# ESP-WROOM32.net
KiCad netlist of a schematic drawn in Altium Designer
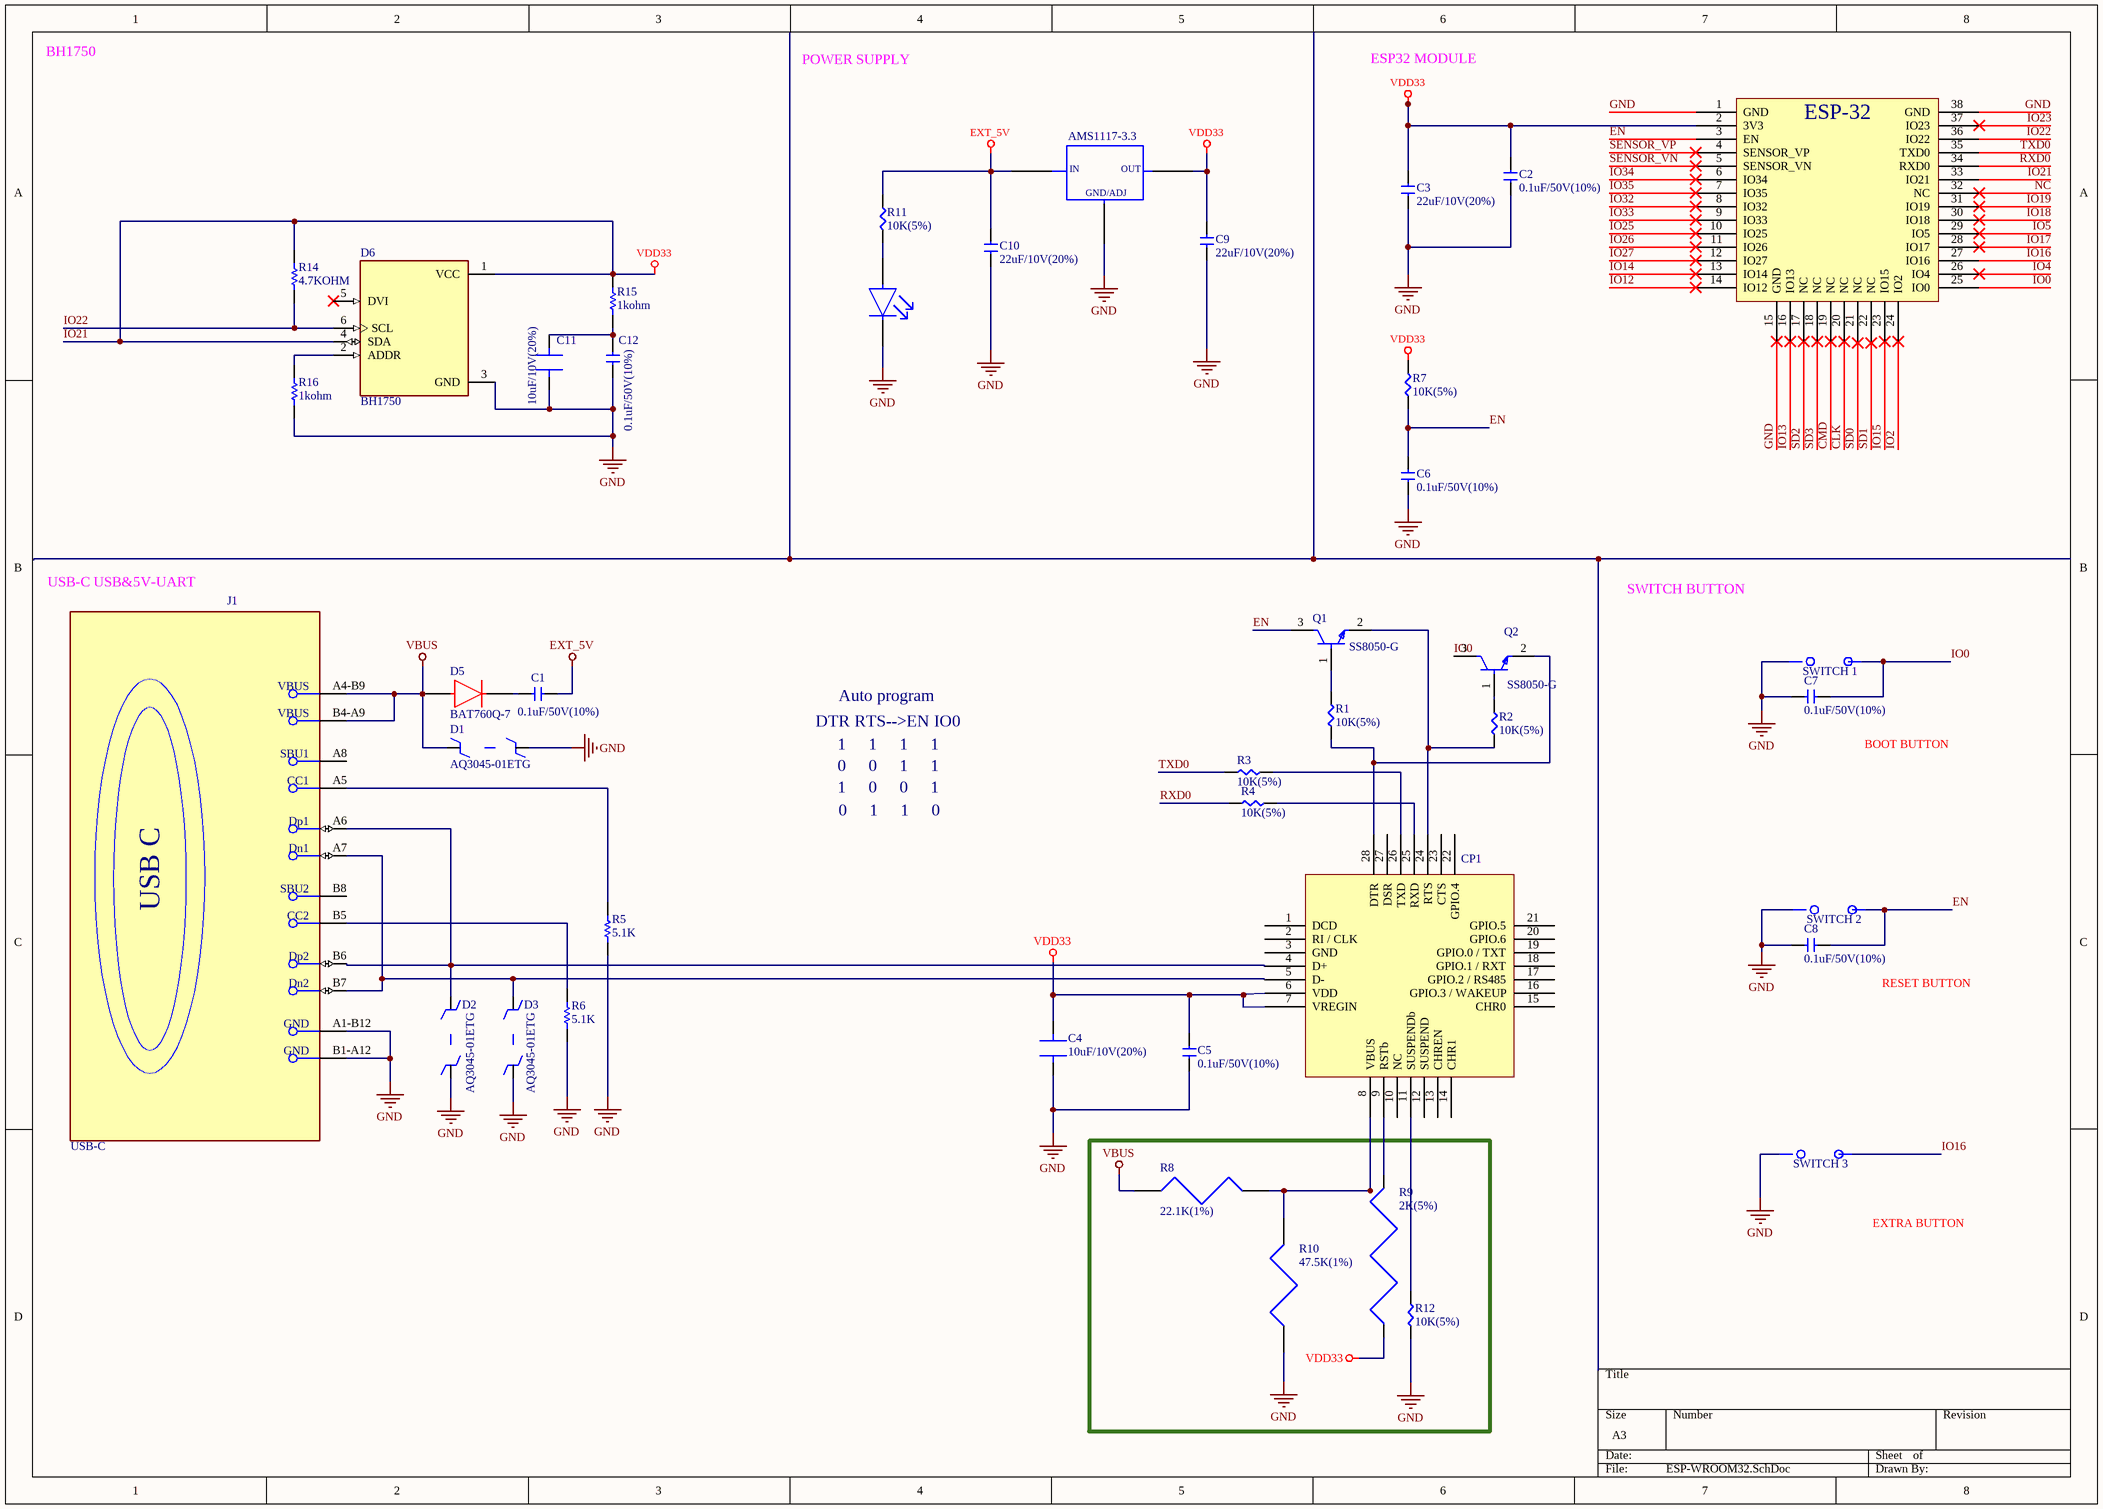
[diagram p0: ESP-WROOM32.SchDoc]

(export (version "E")
  (design (tool "Eeschema 10.0.6"))
  (components
    (comp (ref "*1")
      (value "ESP32-WROOM-32E-N4")
      (footprint "MODULE_ESP-WROOM-32")
      (description "RF TXRX MOD BT WIFI TH SMD")
      (fields (field (name "MANUFACTURER") "Espressif Systems") (field (name "LCSC PART NUMBER") "C701341"))
      (libsource (lib "Librayryschematic") (part "ESP32-WROOM-32E-N4"))
    )
    (comp (ref "C1")
      (value "0.1uF/50V(10%)")
      (footprint "FP-GRM158-0_2-IPC_A")
      (description "CAP CER 0.1UF 50V X7R 0402")
      (fields
        (field (name "MANUFACTURER") "Samsung Electro-Mechanics")
        (field (name "MANUFACTURER PART NUMBER") "CL05B104KB5NNWC")
      )
      (libsource (lib "Librayryschematic") (part "CL05B104KB5NNWC"))
    )
    (comp (ref "C2")
      (value "0.1uF/50V(10%)")
      (footprint "FP-GRM158-0_2-IPC_A")
      (description "CAP CER 0.1UF 50V X7R 0402")
      (fields
        (field (name "MANUFACTURER") "Samsung Electro-Mechanics")
        (field (name "MANUFACTURER PART NUMBER") "CL05B104KB5NNWC")
      )
      (libsource (lib "Librayryschematic") (part "CL05B104KB5NNWC"))
    )
    (comp (ref "C3")
      (value "22uF/10V(20%)")
      (footprint "FP-GRM158-0_2-IPC_A")
      (description "CAP CER 22UF 10V X5R 0402")
      (fields
        (field (name "MANUFACTURER") "Murata")
        (field (name "MANUFACTURER PART NUMBER") "GRM158R61A226ME15D")
      )
      (libsource (lib "Librayryschematic") (part "GRM158R61A226ME15D"))
    )
    (comp (ref "C4")
      (value "10uF/10V(20%)")
      (footprint "FP-GRM158-0_2-IPC_A")
      (description "CAP CER 10UF 10V X5R 0402")
      (fields
        (field (name "MANUFACTURER") "Yageo Group")
        (field (name "MANUFACTURER PART NUMBER") "CC0402MRX5R6BB106")
      )
      (libsource (lib "Librayryschematic") (part "CC0402MRX5R6BB106"))
    )
    (comp (ref "C5")
      (value "0.1uF/50V(10%)")
      (footprint "FP-GRM158-0_2-IPC_A")
      (description "CAP CER 0.1UF 50V X7R 0402")
      (fields
        (field (name "MANUFACTURER") "Samsung Electro-Mechanics")
        (field (name "MANUFACTURER PART NUMBER") "CL05B104KB5NNWC")
      )
      (libsource (lib "Librayryschematic") (part "CL05B104KB5NNWC"))
    )
    (comp (ref "C6")
      (value "0.1uF/50V(10%)")
      (footprint "FP-GRM158-0_2-IPC_A")
      (description "CAP CER 0.1UF 50V X7R 0402")
      (fields
        (field (name "MANUFACTURER") "Samsung Electro-Mechanics")
        (field (name "MANUFACTURER PART NUMBER") "CL05B104KB5NNWC")
      )
      (libsource (lib "Librayryschematic") (part "CL05B104KB5NNWC"))
    )
    (comp (ref "C7")
      (value "0.1uF/50V(10%)")
      (footprint "FP-GRM158-0_2-IPC_A")
      (description "CAP CER 0.1UF 50V X7R 0402")
      (fields
        (field (name "MANUFACTURER") "Samsung Electro-Mechanics")
        (field (name "MANUFACTURER PART NUMBER") "CL05B104KB5NNWC")
      )
      (libsource (lib "Librayryschematic") (part "CL05B104KB5NNWC"))
    )
    (comp (ref "C8")
      (value "0.1uF/50V(10%)")
      (footprint "FP-GRM158-0_2-IPC_A")
      (description "CAP CER 0.1UF 50V X7R 0402")
      (fields
        (field (name "MANUFACTURER") "Samsung Electro-Mechanics")
        (field (name "MANUFACTURER PART NUMBER") "CL05B104KB5NNWC")
      )
      (libsource (lib "Librayryschematic") (part "CL05B104KB5NNWC"))
    )
    (comp (ref "C9")
      (value "22uF/10V(20%)")
      (footprint "FP-GRM158-0_2-IPC_A")
      (description "CAP CER 22UF 10V X5R 0402")
      (fields
        (field (name "MANUFACTURER") "Murata")
        (field (name "MANUFACTURER PART NUMBER") "GRM158R61A226ME15D")
      )
      (libsource (lib "Librayryschematic") (part "GRM158R61A226ME15D"))
    )
    (comp (ref "C10")
      (value "22uF/10V(20%)")
      (footprint "FP-GRM158-0_2-IPC_A")
      (description "CAP CER 22UF 10V X5R 0402")
      (fields
        (field (name "MANUFACTURER") "Murata")
        (field (name "MANUFACTURER PART NUMBER") "GRM158R61A226ME15D")
      )
      (libsource (lib "Librayryschematic") (part "GRM158R61A226ME15D"))
    )
    (comp (ref "C11")
      (value "10uF/10V(20%)")
      (footprint "FP-GRM158-0_2-IPC_A")
      (description "CAP CER 10UF 10V X5R 0402")
      (fields
        (field (name "MANUFACTURER") "Yageo Group")
        (field (name "MANUFACTURER PART NUMBER") "CC0402MRX5R6BB106")
      )
      (libsource (lib "Librayryschematic") (part "CC0402MRX5R6BB106"))
    )
    (comp (ref "C12")
      (value "0.1uF/50V(10%)")
      (footprint "FP-GRM158-0_2-IPC_A")
      (description "CAP CER 0.1UF 50V X7R 0402")
      (fields
        (field (name "MANUFACTURER") "Samsung Electro-Mechanics")
        (field (name "MANUFACTURER PART NUMBER") "CL05B104KB5NNWC")
      )
      (libsource (lib "Librayryschematic") (part "CL05B104KB5NNWC"))
    )
    (comp (ref "CP1")
      (value "CP2102N-A02-GQFN28")
      (footprint "FP-CP2102N-A02-GQFN28-IPC_A")
      (description "USB Bridge, USB to UART USB 2.0 UART Interface 28-QFN (5x5)")
      (fields (field (name "MANUFACTURER") "Silicon Labs") (field (name "LCSC PART NUMBER") "C964632"))
      (libsource (lib "Librayryschematic") (part "CP2102N-A02-GQFN28"))
    )
    (comp (ref "D1")
      (value "AQ3045-01ETG")
      (footprint "PESD5V0U1BA,115")
      (description "TVS DIODE 5.3VWM 12VC SOD882")
      (fields (field (name "MANUFACTURER") "Littelfuse") (field (name "LCSC PART NUMBER") "C3710326"))
      (libsource (lib "Librayryschematic") (part "AQ3045-01ETG"))
    )
    (comp (ref "D2")
      (value "AQ3045-01ETG")
      (footprint "PESD5V0U1BA,115")
      (description "TVS DIODE 5.3VWM 12VC SOD882")
      (fields (field (name "MANUFACTURER") "Littelfuse") (field (name "LCSC PART NUMBER") "C3710326"))
      (libsource (lib "Librayryschematic") (part "AQ3045-01ETG"))
    )
    (comp (ref "D3")
      (value "AQ3045-01ETG")
      (footprint "PESD5V0U1BA,115")
      (description "TVS DIODE 5.3VWM 12VC SOD882")
      (fields (field (name "MANUFACTURER") "Littelfuse") (field (name "LCSC PART NUMBER") "C3710326"))
      (libsource (lib "Librayryschematic") (part "AQ3045-01ETG"))
    )
    (comp (ref "D4")
      (value "LTST-C170GKT")
      (footprint "FP-LTST-C170GKT-MFG")
      (description "LED GREEN CLEAR SMD")
      (fields (field (name "MANUFACTURER") "Lite-On") (field (name "VOLTAGE") "5V"))
      (libsource (lib "Librayryschematic") (part "LTST-C170GKT"))
    )
    (comp (ref "D5")
      (value "BAT760Q-7")
      (footprint "BAT760Q-7")
      (description "DIODE SCHOTTKY 30V 1A SOD323")
      (fields (field (name "MANUFACTURER") "Diodes Inc.") (field (name "LCSC PART NUMBER") "C3759252"))
      (libsource (lib "Librayryschematic") (part "BAT760Q-7"))
    )
    (comp (ref "D6")
      (value "BH1750")
      (footprint "XDCR_BH1750FVI-TR")
      (description "SENSOR OPT 560NM AMBIENT 6WSOF")
      (fields (field (name "MANUFACTURER") "ROHM") (field (name "MANUFACTURER PART NUMBER") "BH1750FVI-TR"))
      (libsource (lib "Librayryschematic") (part "BH1750FVI-TR"))
    )
    (comp (ref "J1")
      (value "USB-C")
      (footprint "FP-2171790001-MFG")
      (description "CONN RCP USB2.0 TYP C 24P SMD RA")
      (fields (field (name "MANUFACTURER") "Molex") (field (name "MANUFACTURER PART NUMBER") "217179-0001"))
      (libsource (lib "Librayryschematic") (part "2171790001"))
    )
    (comp (ref "Q1")
      (value "SS8050-G")
      (footprint "FP-SS8050-G-IPC_A")
      (description "TRANS NPN 25V 1.5A SOT-23-3")
      (fields (field (name "MANUFACTURER") "Comchip") (field (name "LCSC PART NUMBER") "C164886"))
      (libsource (lib "Librayryschematic") (part "SS8050-G"))
    )
    (comp (ref "Q2")
      (value "SS8050-G")
      (footprint "FP-SS8050-G-IPC_A")
      (description "TRANS NPN 25V 1.5A SOT-23-3")
      (fields (field (name "MANUFACTURER") "Comchip") (field (name "LCSC PART NUMBER") "C164886"))
      (libsource (lib "Librayryschematic") (part "SS8050-G"))
    )
    (comp (ref "R1")
      (value "10K(5%)")
      (footprint "RESC1005X40X25LL05T10")
      (description "RES 10K OHM 5% 1/16W 0402")
      (fields
        (field (name "MANUFACTURER") "Yageo Group")
        (field (name "MANUFACTURER PART NUMBER") "RC0402JR-0710KL")
      )
      (libsource (lib "Librayryschematic") (part "RC0402JR-0710KL"))
    )
    (comp (ref "R2")
      (value "10K(5%)")
      (footprint "RESC1005X40X25LL05T10")
      (description "RES 10K OHM 5% 1/16W 0402")
      (fields
        (field (name "MANUFACTURER") "Yageo Group")
        (field (name "MANUFACTURER PART NUMBER") "RC0402JR-0710KL")
      )
      (libsource (lib "Librayryschematic") (part "RC0402JR-0710KL"))
    )
    (comp (ref "R3")
      (value "10K(5%)")
      (footprint "RESC1005X40X25LL05T10")
      (description "RES 10K OHM 5% 1/16W 0402")
      (fields
        (field (name "MANUFACTURER") "Yageo Group")
        (field (name "MANUFACTURER PART NUMBER") "RC0402JR-0710KL")
      )
      (libsource (lib "Librayryschematic") (part "RC0402JR-0710KL"))
    )
    (comp (ref "R4")
      (value "10K(5%)")
      (footprint "RESC1005X40X25LL05T10")
      (description "RES 10K OHM 5% 1/16W 0402")
      (fields
        (field (name "MANUFACTURER") "Yageo Group")
        (field (name "MANUFACTURER PART NUMBER") "RC0402JR-0710KL")
      )
      (libsource (lib "Librayryschematic") (part "RC0402JR-0710KL"))
    )
    (comp (ref "R5")
      (value "5.1K")
      (footprint "RESC1005X40X25LL05T10")
      (description "RES 5.1K OHM 1% 1/16W 0402")
      (fields
        (field (name "MANUFACTURER") "Yageo Group")
        (field (name "MANUFACTURER PART NUMBER") "RC0402FR-075K1L")
      )
      (libsource (lib "Librayryschematic") (part "RC0402FR-075K1L"))
    )
    (comp (ref "R6")
      (value "5.1K")
      (footprint "RESC1005X40X25LL05T10")
      (description "RES 5.1K OHM 1% 1/16W 0402")
      (fields
        (field (name "MANUFACTURER") "Yageo Group")
        (field (name "MANUFACTURER PART NUMBER") "RC0402FR-075K1L")
      )
      (libsource (lib "Librayryschematic") (part "RC0402FR-075K1L"))
    )
    (comp (ref "R7")
      (value "10K(5%)")
      (footprint "RESC1005X40X25LL05T10")
      (description "RES 10K OHM 5% 1/16W 0402")
      (fields
        (field (name "MANUFACTURER") "Yageo Group")
        (field (name "MANUFACTURER PART NUMBER") "RC0402JR-0710KL")
      )
      (libsource (lib "Librayryschematic") (part "RC0402JR-0710KL"))
    )
    (comp (ref "R8")
      (value "22.1K(1%)")
      (footprint "RESC1005X40X25LL05T10")
      (description "RES SMD 22.1K OHM 1% 1/16W 0402")
      (fields
        (field (name "MANUFACTURER") "Yageo Group")
        (field (name "MANUFACTURER PART NUMBER") "AC0402FR-0722K1L")
      )
      (libsource (lib "Librayryschematic") (part "AC0402FR-0722K1L"))
    )
    (comp (ref "R9")
      (value "2K(5%)")
      (footprint "RESC1005X40X25LL05T10")
      (description "RES 2K OHM 5% 1/16W 0402")
      (fields
        (field (name "MANUFACTURER") "Yageo Group")
        (field (name "MANUFACTURER PART NUMBER") "RC0402JR-072KL")
      )
      (libsource (lib "Librayryschematic") (part "RC0402JR-072KL"))
    )
    (comp (ref "R10")
      (value "47.5K(1%)")
      (footprint "RESC1005X40X25LL05T10")
      (description "RES 47.5K OHM 1% 1/16W 0402")
      (fields
        (field (name "MANUFACTURER") "Yageo Group")
        (field (name "MANUFACTURER PART NUMBER") "RC0402FR-1347K5L")
      )
      (libsource (lib "Librayryschematic") (part "RC0402FR-1347K5L"))
    )
    (comp (ref "R11")
      (value "10K(5%)")
      (footprint "RESC1005X40X25LL05T10")
      (description "RES 10K OHM 5% 1/16W 0402")
      (fields
        (field (name "MANUFACTURER") "Yageo Group")
        (field (name "MANUFACTURER PART NUMBER") "RC0402JR-0710KL")
      )
      (libsource (lib "Librayryschematic") (part "RC0402JR-0710KL"))
    )
    (comp (ref "R12")
      (value "10K(5%)")
      (footprint "RESC1005X40X25LL05T10")
      (description "RES 10K OHM 5% 1/16W 0402")
      (fields
        (field (name "MANUFACTURER") "Yageo Group")
        (field (name "MANUFACTURER PART NUMBER") "RC0402JR-0710KL")
      )
      (libsource (lib "Librayryschematic") (part "RC0402JR-0710KL"))
    )
    (comp (ref "R14")
      (value "4.7KOHM")
      (footprint "RESC1005X40X25LL05T10")
      (description "RES 4.7K OHM 5% 1/16W 0402")
      (fields
        (field (name "MANUFACTURER") "Yageo Group")
        (field (name "MANUFACTURER PART NUMBER") "RC0402JR-0747KL")
      )
      (libsource (lib "Librayryschematic") (part "RC0402JR-0747KL"))
    )
    (comp (ref "R15")
      (value "1kohm")
      (footprint "RESC1005X40X25LL05T10")
      (description "RES 1K OHM 5% 1/16W 0402")
      (fields
        (field (name "MANUFACTURER") "Yageo Group")
        (field (name "MANUFACTURER PART NUMBER") "RC0402JR-071KL")
      )
      (libsource (lib "Librayryschematic") (part "RC0402JR-071KL"))
    )
    (comp (ref "R16")
      (value "1kohm")
      (footprint "RESC1005X40X25LL05T10")
      (description "RES 1K OHM 5% 1/16W 0402")
      (fields
        (field (name "MANUFACTURER") "Yageo Group")
        (field (name "MANUFACTURER PART NUMBER") "RC0402JR-071KL")
      )
      (libsource (lib "Librayryschematic") (part "RC0402JR-071KL"))
    )
    (comp (ref "SWITCH 1")
      (value "PTS645SL50SMTR92LFS")
      (footprint "FP-PTS645SH50SMTR92LFS-MFG")
      (description "SWITCH TACTILE SPST-NO 0.05A 12V")
      (fields (field (name "MANUFACTURER") "C&K Components") (field (name "LCSC PART NUMBER") "C221877"))
      (libsource (lib "Librayryschematic") (part "PTS645SL50SMTR92LFS"))
    )
    (comp (ref "SWITCH 2")
      (value "PTS645SL50SMTR92LFS")
      (footprint "FP-PTS645SH50SMTR92LFS-MFG")
      (description "SWITCH TACTILE SPST-NO 0.05A 12V")
      (fields (field (name "MANUFACTURER") "C&K Components") (field (name "LCSC PART NUMBER") "C221877"))
      (libsource (lib "Librayryschematic") (part "PTS645SL50SMTR92LFS"))
    )
    (comp (ref "SWITCH 3")
      (value "PTS645SL50SMTR92LFS")
      (footprint "FP-PTS645SH50SMTR92LFS-MFG")
      (description "SWITCH TACTILE SPST-NO 0.05A 12V")
      (fields (field (name "MANUFACTURER") "C&K Components") (field (name "LCSC PART NUMBER") "C221877"))
      (libsource (lib "Librayryschematic") (part "PTS645SL50SMTR92LFS"))
    )
    (comp (ref "U1")
      (value "AMS1117-3.3")
      (footprint "FP-AMS1117-IPC_A")
      (description "IC REG LINEAR 3.3V 1A SOT-223")
      (fields
        (field (name "MANUFACTURER") "UMW(Youtai Semiconductor Co., Ltd.)")
        (field (name "LCSC PART NUMBER") "C6186")
      )
      (libsource (lib "Librayryschematic") (part "AMS1117-3.3"))
    )
  )
  (nets
    (net (code "1") (name "/CLK") (class "Default")
      (node (ref "*1") (pin "20") (pinfunction "NC_20") (pintype "passive+no_connect"))
    )
    (net (code "2") (name "/CMD") (class "Default")
      (node (ref "*1") (pin "19") (pinfunction "NC_19") (pintype "passive+no_connect"))
    )
    (net (code "3") (name "/EN") (class "Default")
      (node (ref "*1") (pin "3") (pinfunction "EN_3") (pintype "passive"))
      (node (ref "C6") (pin "2") (pinfunction "2_2") (pintype "passive"))
      (node (ref "C8") (pin "2") (pinfunction "2_2") (pintype "passive"))
      (node (ref "Q1") (pin "3") (pinfunction "C_3") (pintype "passive"))
      (node (ref "R7") (pin "1") (pinfunction "1_1") (pintype "passive"))
      (node (ref "SWITCH 2") (pin "3") (pinfunction "3_3") (pintype "passive"))
    )
    (net (code "4") (name "/IO0") (class "Default")
      (node (ref "*1") (pin "25") (pinfunction "IO0_25") (pintype "passive"))
      (node (ref "C7") (pin "2") (pinfunction "2_2") (pintype "passive"))
      (node (ref "Q2") (pin "3") (pinfunction "C_3") (pintype "passive"))
      (node (ref "SWITCH 1") (pin "3") (pinfunction "3_3") (pintype "passive"))
    )
    (net (code "5") (name "/IO2") (class "Default")
      (node (ref "*1") (pin "24") (pinfunction "IO2_24") (pintype "passive+no_connect"))
    )
    (net (code "6") (name "/IO4") (class "Default")
      (node (ref "*1") (pin "26") (pinfunction "IO4_26") (pintype "passive+no_connect"))
    )
    (net (code "7") (name "/IO5") (class "Default")
      (node (ref "*1") (pin "29") (pinfunction "IO5_29") (pintype "passive+no_connect"))
    )
    (net (code "8") (name "/IO12") (class "Default")
      (node (ref "*1") (pin "14") (pinfunction "IO12_14") (pintype "passive+no_connect"))
    )
    (net (code "9") (name "/IO13") (class "Default")
      (node (ref "*1") (pin "16") (pinfunction "IO13_16") (pintype "passive+no_connect"))
    )
    (net (code "10") (name "/IO14") (class "Default")
      (node (ref "*1") (pin "13") (pinfunction "IO14_13") (pintype "passive+no_connect"))
    )
    (net (code "11") (name "/IO15") (class "Default")
      (node (ref "*1") (pin "23") (pinfunction "IO15_23") (pintype "passive+no_connect"))
    )
    (net (code "12") (name "/IO16") (class "Default")
      (node (ref "*1") (pin "27") (pinfunction "IO16_27") (pintype "passive"))
      (node (ref "SWITCH 3") (pin "3") (pinfunction "3_3") (pintype "passive"))
    )
    (net (code "13") (name "/IO17") (class "Default")
      (node (ref "*1") (pin "28") (pinfunction "IO17_28") (pintype "passive+no_connect"))
    )
    (net (code "14") (name "/IO18") (class "Default")
      (node (ref "*1") (pin "30") (pinfunction "IO18_30") (pintype "passive+no_connect"))
    )
    (net (code "15") (name "/IO19") (class "Default")
      (node (ref "*1") (pin "31") (pinfunction "IO19_31") (pintype "passive+no_connect"))
    )
    (net (code "16") (name "/IO22") (class "Default")
      (node (ref "*1") (pin "36") (pinfunction "IO22_36") (pintype "passive"))
      (node (ref "D6") (pin "6") (pinfunction "SCL_6") (pintype "input"))
      (node (ref "R14") (pin "2") (pinfunction "2_2") (pintype "passive"))
    )
    (net (code "17") (name "/IO23") (class "Default")
      (node (ref "*1") (pin "37") (pinfunction "IO23_37") (pintype "passive+no_connect"))
    )
    (net (code "18") (name "/IO25") (class "Default")
      (node (ref "*1") (pin "10") (pinfunction "IO25_10") (pintype "passive+no_connect"))
    )
    (net (code "19") (name "/IO26") (class "Default")
      (node (ref "*1") (pin "11") (pinfunction "IO26_11") (pintype "passive+no_connect"))
    )
    (net (code "20") (name "/IO27") (class "Default")
      (node (ref "*1") (pin "12") (pinfunction "IO27_12") (pintype "passive+no_connect"))
    )
    (net (code "21") (name "/IO32") (class "Default")
      (node (ref "*1") (pin "8") (pinfunction "IO32_8") (pintype "passive+no_connect"))
    )
    (net (code "22") (name "/IO33") (class "Default")
      (node (ref "*1") (pin "9") (pinfunction "IO33_9") (pintype "passive+no_connect"))
    )
    (net (code "23") (name "/IO34") (class "Default")
      (node (ref "*1") (pin "6") (pinfunction "IO34_6") (pintype "passive+no_connect"))
    )
    (net (code "24") (name "/IO35") (class "Default")
      (node (ref "*1") (pin "7") (pinfunction "IO35_7") (pintype "passive+no_connect"))
    )
    (net (code "25") (name "/NC") (class "Default")
      (node (ref "*1") (pin "32") (pinfunction "NC_32") (pintype "passive+no_connect"))
    )
    (net (code "26") (name "/RXD0") (class "Default")
      (node (ref "*1") (pin "34") (pinfunction "RXD0_34") (pintype "passive"))
      (node (ref "R4") (pin "1") (pinfunction "1_1") (pintype "passive"))
    )
    (net (code "27") (name "/SD0") (class "Default")
      (node (ref "*1") (pin "21") (pinfunction "NC_21") (pintype "passive"))
    )
    (net (code "28") (name "/SD1") (class "Default")
      (node (ref "*1") (pin "22") (pinfunction "NC_22") (pintype "passive"))
    )
    (net (code "29") (name "/SD2") (class "Default")
      (node (ref "*1") (pin "17") (pinfunction "NC_17") (pintype "passive+no_connect"))
    )
    (net (code "30") (name "/SD3") (class "Default")
      (node (ref "*1") (pin "18") (pinfunction "NC_18") (pintype "passive+no_connect"))
    )
    (net (code "31") (name "/SENSOR_VN") (class "Default")
      (node (ref "*1") (pin "5") (pinfunction "SENSOR_VN_5") (pintype "passive+no_connect"))
    )
    (net (code "32") (name "/SENSOR_VP") (class "Default")
      (node (ref "*1") (pin "4") (pinfunction "SENSOR_VP_4") (pintype "passive+no_connect"))
    )
    (net (code "33") (name "/TXD0") (class "Default")
      (node (ref "*1") (pin "35") (pinfunction "TXD0_35") (pintype "passive"))
      (node (ref "R3") (pin "1") (pinfunction "1_1") (pintype "passive"))
    )
    (net (code "34") (name "EXT_5V") (class "Default")
      (node (ref "C1") (pin "2") (pinfunction "2_2") (pintype "passive"))
      (node (ref "C10") (pin "2") (pinfunction "2_2") (pintype "passive"))
      (node (ref "R11") (pin "2") (pinfunction "2_2") (pintype "passive"))
      (node (ref "U1") (pin "1") (pinfunction "1_1") (pintype "passive"))
    )
    (net (code "35") (name "GND") (class "Default")
      (node (ref "*1") (pin "1") (pinfunction "GND_1") (pintype "passive"))
      (node (ref "*1") (pin "15") (pinfunction "GND_15") (pintype "passive"))
      (node (ref "*1") (pin "38") (pinfunction "GND_38") (pintype "passive"))
      (node (ref "C10") (pin "1") (pinfunction "1_1") (pintype "passive"))
      (node (ref "C11") (pin "1") (pinfunction "1_1") (pintype "passive"))
      (node (ref "C12") (pin "1") (pinfunction "1_1") (pintype "passive"))
      (node (ref "C2") (pin "1") (pinfunction "1_1") (pintype "passive"))
      (node (ref "C3") (pin "1") (pinfunction "1_1") (pintype "passive"))
      (node (ref "C4") (pin "1") (pinfunction "1_1") (pintype "passive"))
      (node (ref "C5") (pin "1") (pinfunction "1_1") (pintype "passive"))
      (node (ref "C6") (pin "1") (pinfunction "1_1") (pintype "passive"))
      (node (ref "C7") (pin "1") (pinfunction "1_1") (pintype "passive"))
      (node (ref "C8") (pin "1") (pinfunction "1_1") (pintype "passive"))
      (node (ref "C9") (pin "1") (pinfunction "1_1") (pintype "passive"))
      (node (ref "D1") (pin "2") (pinfunction "2_2") (pintype "passive"))
      (node (ref "D2") (pin "2") (pinfunction "2_2") (pintype "passive"))
      (node (ref "D3") (pin "2") (pinfunction "2_2") (pintype "passive"))
      (node (ref "D4") (pin "2") (pinfunction "2_2") (pintype "passive"))
      (node (ref "D6") (pin "3") (pinfunction "GND_3") (pintype "power_in"))
      (node (ref "J1") (pin "A1-B12") (pinfunction "GND_A1-B12") (pintype "power_in"))
      (node (ref "J1") (pin "B1-A12") (pinfunction "GND_B1-A12") (pintype "power_in"))
      (node (ref "R10") (pin "1") (pinfunction "1_1") (pintype "passive"))
      (node (ref "R12") (pin "1") (pinfunction "1_1") (pintype "passive"))
      (node (ref "R16") (pin "1") (pinfunction "1_1") (pintype "passive"))
      (node (ref "R5") (pin "1") (pinfunction "1_1") (pintype "passive"))
      (node (ref "R6") (pin "1") (pinfunction "1_1") (pintype "passive"))
      (node (ref "SWITCH 1") (pin "4") (pinfunction "4_4") (pintype "passive"))
      (node (ref "SWITCH 2") (pin "4") (pinfunction "4_4") (pintype "passive"))
      (node (ref "SWITCH 3") (pin "4") (pinfunction "4_4") (pintype "passive"))
      (node (ref "U1") (pin "3") (pinfunction "3_3") (pintype "passive"))
    )
    (net (code "36") (name "Net-(C1-Pad1)") (class "Default")
      (node (ref "C1") (pin "1") (pinfunction "1_1") (pintype "passive"))
      (node (ref "D5") (pin "2") (pinfunction "2_2") (pintype "passive"))
    )
    (net (code "37") (name "Net-(C11-Pad2)") (class "Default")
      (node (ref "C11") (pin "2") (pinfunction "2_2") (pintype "passive"))
      (node (ref "C12") (pin "2") (pinfunction "2_2") (pintype "passive"))
      (node (ref "R15") (pin "1") (pinfunction "1_1") (pintype "passive"))
    )
    (net (code "38") (name "Net-(CP1-D+)") (class "Default")
      (node (ref "CP1") (pin "4") (pinfunction "D+_4") (pintype "passive"))
      (node (ref "D2") (pin "1") (pinfunction "1_1") (pintype "passive"))
      (node (ref "J1") (pin "A6") (pinfunction "Dp1_A6") (pintype "bidirectional"))
      (node (ref "J1") (pin "B6") (pinfunction "Dp2_B6") (pintype "bidirectional"))
    )
    (net (code "39") (name "Net-(CP1-D-)") (class "Default")
      (node (ref "CP1") (pin "5") (pinfunction "D-_5") (pintype "passive"))
      (node (ref "D3") (pin "1") (pinfunction "1_1") (pintype "passive"))
      (node (ref "J1") (pin "A7") (pinfunction "Dn1_A7") (pintype "bidirectional"))
      (node (ref "J1") (pin "B7") (pinfunction "Dn2_B7") (pintype "bidirectional"))
    )
    (net (code "40") (name "Net-(CP1-DTR)") (class "Default")
      (node (ref "CP1") (pin "28") (pinfunction "DTR_28") (pintype "passive"))
      (node (ref "Q2") (pin "2") (pinfunction "E_2") (pintype "passive"))
      (node (ref "R1") (pin "1") (pinfunction "1_1") (pintype "passive"))
    )
    (net (code "41") (name "Net-(CP1-RSTb)") (class "Default")
      (node (ref "CP1") (pin "9") (pinfunction "RSTb_9") (pintype "passive"))
      (node (ref "R9") (pin "2") (pinfunction "2_2") (pintype "passive"))
    )
    (net (code "42") (name "Net-(CP1-RTS)") (class "Default")
      (node (ref "CP1") (pin "24") (pinfunction "RTS_24") (pintype "passive"))
      (node (ref "Q1") (pin "2") (pinfunction "E_2") (pintype "passive"))
      (node (ref "R2") (pin "1") (pinfunction "1_1") (pintype "passive"))
    )
    (net (code "43") (name "Net-(CP1-RXD)") (class "Default")
      (node (ref "CP1") (pin "25") (pinfunction "RXD_25") (pintype "passive"))
      (node (ref "R4") (pin "2") (pinfunction "2_2") (pintype "passive"))
    )
    (net (code "44") (name "Net-(CP1-SUSPENDb)") (class "Default")
      (node (ref "CP1") (pin "11") (pinfunction "SUSPENDb_11") (pintype "passive"))
      (node (ref "R12") (pin "2") (pinfunction "2_2") (pintype "passive"))
    )
    (net (code "45") (name "Net-(CP1-TXD)") (class "Default")
      (node (ref "CP1") (pin "26") (pinfunction "TXD_26") (pintype "passive"))
      (node (ref "R3") (pin "2") (pinfunction "2_2") (pintype "passive"))
    )
    (net (code "46") (name "Net-(CP1-VBUS)") (class "Default")
      (node (ref "CP1") (pin "8") (pinfunction "VBUS_8") (pintype "passive"))
      (node (ref "R10") (pin "2") (pinfunction "2_2") (pintype "passive"))
      (node (ref "R8") (pin "2") (pinfunction "2_2") (pintype "passive"))
    )
    (net (code "47") (name "Net-(D4-Pad1)") (class "Default")
      (node (ref "D4") (pin "1") (pinfunction "1_1") (pintype "passive"))
      (node (ref "R11") (pin "1") (pinfunction "1_1") (pintype "passive"))
    )
    (net (code "48") (name "Net-(D6-ADDR)") (class "Default")
      (node (ref "D6") (pin "2") (pinfunction "ADDR_2") (pintype "input"))
      (node (ref "R16") (pin "2") (pinfunction "2_2") (pintype "passive"))
    )
    (net (code "49") (name "Net-(J1-CC1)") (class "Default")
      (node (ref "J1") (pin "A5") (pinfunction "CC1_A5") (pintype "passive"))
      (node (ref "R5") (pin "2") (pinfunction "2_2") (pintype "passive"))
    )
    (net (code "50") (name "Net-(J1-CC2)") (class "Default")
      (node (ref "J1") (pin "B5") (pinfunction "CC2_B5") (pintype "passive"))
      (node (ref "R6") (pin "2") (pinfunction "2_2") (pintype "passive"))
    )
    (net (code "51") (name "Net-(Q1-B)") (class "Default")
      (node (ref "Q1") (pin "1") (pinfunction "B_1") (pintype "passive"))
      (node (ref "R1") (pin "2") (pinfunction "2_2") (pintype "passive"))
    )
    (net (code "52") (name "Net-(Q2-B)") (class "Default")
      (node (ref "Q2") (pin "1") (pinfunction "B_1") (pintype "passive"))
      (node (ref "R2") (pin "2") (pinfunction "2_2") (pintype "passive"))
    )
    (net (code "53") (name "VBUS") (class "Default")
      (node (ref "D1") (pin "1") (pinfunction "1_1") (pintype "passive"))
      (node (ref "D5") (pin "1") (pinfunction "1_1") (pintype "passive"))
      (node (ref "J1") (pin "A4-B9") (pinfunction "VBUS_A4-B9") (pintype "power_in"))
      (node (ref "J1") (pin "B4-A9") (pinfunction "VBUS_B4-A9") (pintype "power_in"))
      (node (ref "R8") (pin "1") (pinfunction "1_1") (pintype "passive"))
    )
    (net (code "54") (name "VDD33") (class "Default")
      (node (ref "*1") (pin "2") (pinfunction "3V3_2") (pintype "passive"))
      (node (ref "*1") (pin "33") (pinfunction "IO21_33") (pintype "passive"))
      (node (ref "C2") (pin "2") (pinfunction "2_2") (pintype "passive"))
      (node (ref "C3") (pin "2") (pinfunction "2_2") (pintype "passive"))
      (node (ref "C4") (pin "2") (pinfunction "2_2") (pintype "passive"))
      (node (ref "C5") (pin "2") (pinfunction "2_2") (pintype "passive"))
      (node (ref "C9") (pin "2") (pinfunction "2_2") (pintype "passive"))
      (node (ref "CP1") (pin "6") (pinfunction "VDD_6") (pintype "passive"))
      (node (ref "CP1") (pin "7") (pinfunction "VREGIN_7") (pintype "passive"))
      (node (ref "D6") (pin "1") (pinfunction "VCC_1") (pintype "power_in"))
      (node (ref "D6") (pin "4") (pinfunction "SDA_4") (pintype "bidirectional"))
      (node (ref "R14") (pin "1") (pinfunction "1_1") (pintype "passive"))
      (node (ref "R15") (pin "2") (pinfunction "2_2") (pintype "passive"))
      (node (ref "R7") (pin "2") (pinfunction "2_2") (pintype "passive"))
      (node (ref "R9") (pin "1") (pinfunction "1_1") (pintype "passive"))
      (node (ref "U1") (pin "2") (pinfunction "2_2") (pintype "passive"))
    )
    (net (code "55") (name "unconnected-(CP1-CHR0-Pad15)") (class "Default")
      (node (ref "CP1") (pin "15") (pinfunction "CHR0_15") (pintype "passive"))
    )
    (net (code "56") (name "unconnected-(CP1-CHR1-Pad14)") (class "Default")
      (node (ref "CP1") (pin "14") (pinfunction "CHR1_14") (pintype "passive"))
    )
    (net (code "57") (name "unconnected-(CP1-CHREN-Pad13)") (class "Default")
      (node (ref "CP1") (pin "13") (pinfunction "CHREN_13") (pintype "passive"))
    )
    (net (code "58") (name "unconnected-(CP1-CTS-Pad23)") (class "Default")
      (node (ref "CP1") (pin "23") (pinfunction "CTS_23") (pintype "passive"))
    )
    (net (code "59") (name "unconnected-(CP1-DCD-Pad1)") (class "Default")
      (node (ref "CP1") (pin "1") (pinfunction "DCD_1") (pintype "passive"))
    )
    (net (code "60") (name "unconnected-(CP1-DSR-Pad27)") (class "Default")
      (node (ref "CP1") (pin "27") (pinfunction "DSR_27") (pintype "passive"))
    )
    (net (code "61") (name "unconnected-(CP1-GND-Pad3)") (class "Default")
      (node (ref "CP1") (pin "3") (pinfunction "GND_3") (pintype "passive"))
    )
    (net (code "62") (name "unconnected-(CP1-GPIO.0_{slash}_TXT-Pad19)") (class "Default")
      (node (ref "CP1") (pin "19") (pinfunction "GPIO.0_/_TXT_19") (pintype "passive"))
    )
    (net (code "63") (name "unconnected-(CP1-GPIO.1_{slash}_RXT-Pad18)") (class "Default")
      (node (ref "CP1") (pin "18") (pinfunction "GPIO.1_/_RXT_18") (pintype "passive"))
    )
    (net (code "64") (name "unconnected-(CP1-GPIO.2_{slash}_RS485-Pad17)") (class "Default")
      (node (ref "CP1") (pin "17") (pinfunction "GPIO.2_/_RS485_17") (pintype "passive"))
    )
    (net (code "65") (name "unconnected-(CP1-GPIO.3_{slash}_WAKEUP-Pad16)") (class "Default")
      (node (ref "CP1") (pin "16") (pinfunction "GPIO.3_/_WAKEUP_16") (pintype "passive"))
    )
    (net (code "66") (name "unconnected-(CP1-GPIO.4-Pad22)") (class "Default")
      (node (ref "CP1") (pin "22") (pinfunction "GPIO.4_22") (pintype "passive"))
    )
    (net (code "67") (name "unconnected-(CP1-GPIO.5-Pad21)") (class "Default")
      (node (ref "CP1") (pin "21") (pinfunction "GPIO.5_21") (pintype "passive"))
    )
    (net (code "68") (name "unconnected-(CP1-GPIO.6-Pad20)") (class "Default")
      (node (ref "CP1") (pin "20") (pinfunction "GPIO.6_20") (pintype "passive"))
    )
    (net (code "69") (name "unconnected-(CP1-NC-Pad10)") (class "Default")
      (node (ref "CP1") (pin "10") (pinfunction "NC_10") (pintype "passive"))
    )
    (net (code "70") (name "unconnected-(CP1-RI_{slash}_CLK-Pad2)") (class "Default")
      (node (ref "CP1") (pin "2") (pinfunction "RI_/_CLK_2") (pintype "passive"))
    )
    (net (code "71") (name "unconnected-(CP1-SUSPEND-Pad12)") (class "Default")
      (node (ref "CP1") (pin "12") (pinfunction "SUSPEND_12") (pintype "passive"))
    )
    (net (code "72") (name "unconnected-(D6-DVI-Pad5)") (class "Default")
      (node (ref "D6") (pin "5") (pinfunction "DVI_5") (pintype "input+no_connect"))
    )
    (net (code "73") (name "unconnected-(J1-SBU1-PadA8)") (class "Default")
      (node (ref "J1") (pin "A8") (pinfunction "SBU1_A8") (pintype "passive"))
    )
    (net (code "74") (name "unconnected-(J1-SBU2-PadB8)") (class "Default")
      (node (ref "J1") (pin "B8") (pinfunction "SBU2_B8") (pintype "passive"))
    )
  )
)
